# NTC_Thermistor_10K_VDiv.net
KiCad netlist of a schematic drawn in Altium Designer
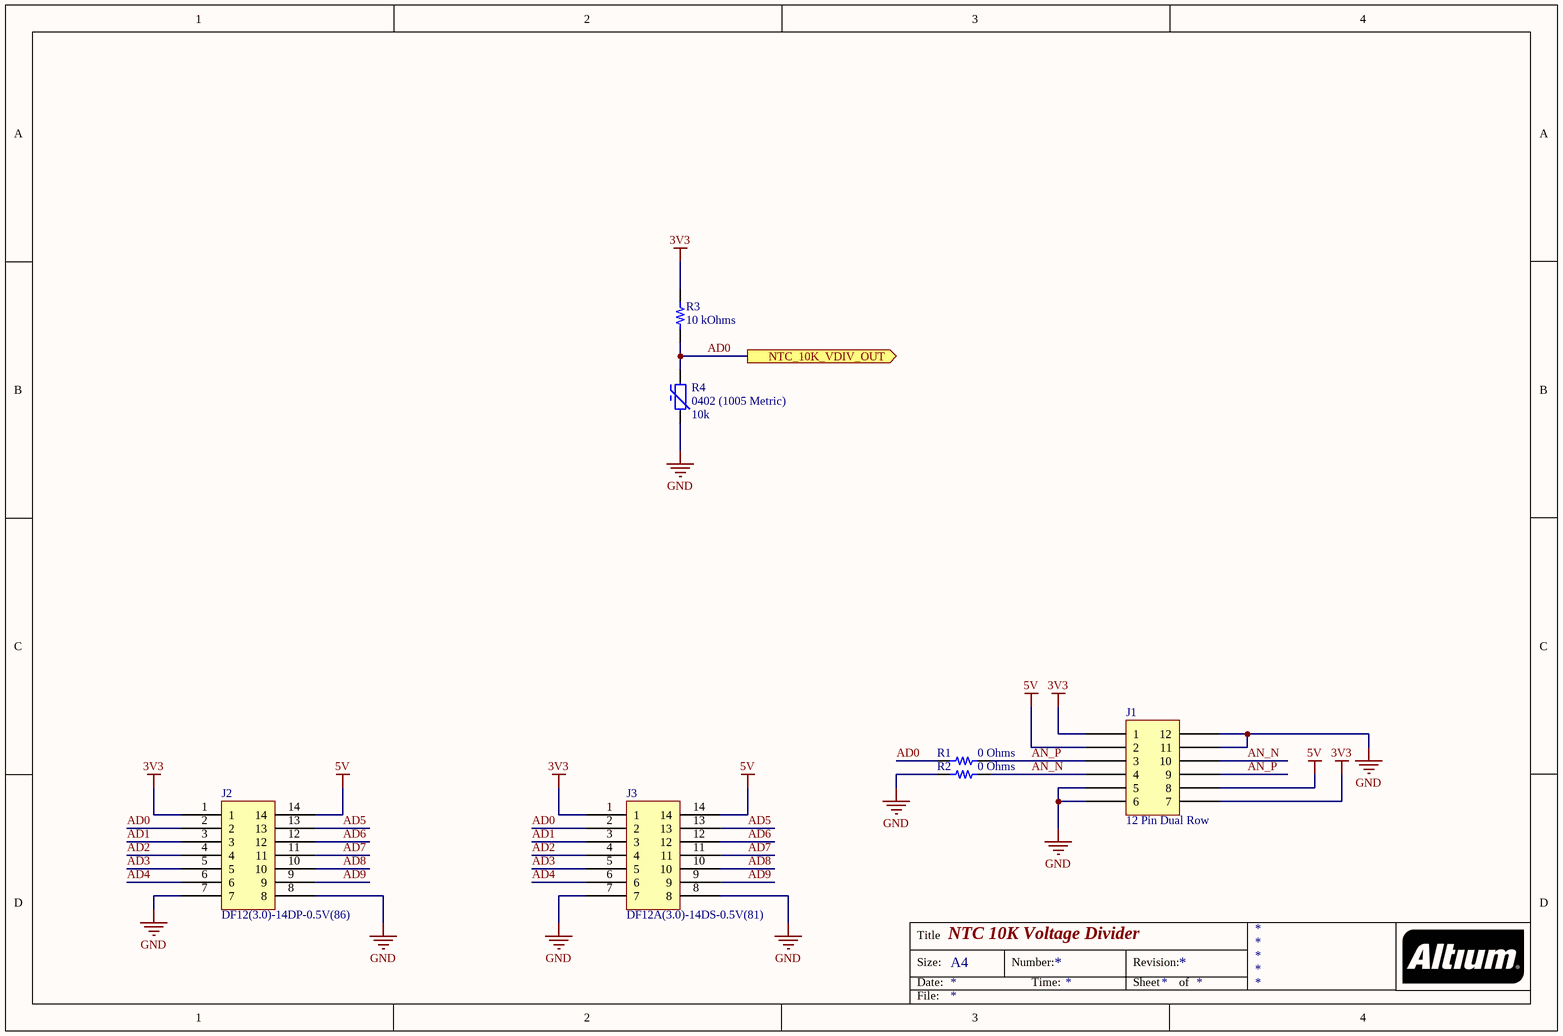
[diagram p0: NTC Thermistor 10K VDiv.SchDoc]

(export (version "E")
  (design (tool "Eeschema 10.0.6"))
  (components
    (comp (ref "J1")
      (value "12 Pin Dual Row")
      (footprint "TE 5650118-3 Card Edge")
      (libsource (lib "CelestialUseful") (part "12 Pin Dual Row"))
    )
    (comp (ref "J2")
      (value "DF12(3.0)-14DP-0.5V(86)")
      (footprint "HIROSE DF12 3.0-14DP-0.5V 86")
      (description "CONN HDR 14POS SMD GOLD")
      (fields (field (name "MANUFACTURER") "Hirose Electric Co Ltd"))
      (libsource (lib "altiumlibrary.com") (part "14 Pin Dual Row"))
    )
    (comp (ref "J3")
      (value "DF12A(3.0)-14DS-0.5V(81)")
      (footprint "HIROSE DF12A 3.0-14DS-0.5V 81")
      (description "CONN RCPT 14POS SMD GOLD")
      (fields (field (name "MANUFACTURER") "Hirose Electric Co Ltd"))
      (libsource (lib "altiumlibrary.com") (part "14 Pin Dual Row"))
    )
    (comp (ref "R1")
      (value "0 Ohms")
      (footprint "RES 0603_1608")
      (description "RES SMD 0 OHM JUMPER 1/10W 0603")
      (fields
        (field (name "PART NUMBER") "ERJ-3GEY0R00V")
        (field (name "MANUFACTURER") "Panasonic Electronic Components")
      )
      (libsource (lib "altiumlibrary.com") (part "Resistor"))
    )
    (comp (ref "R2")
      (value "0 Ohms")
      (footprint "RES 0603_1608")
      (description "RES SMD 0 OHM JUMPER 1/10W 0603")
      (fields
        (field (name "PART NUMBER") "ERJ-3GEY0R00V")
        (field (name "MANUFACTURER") "Panasonic Electronic Components")
      )
      (libsource (lib "altiumlibrary.com") (part "Resistor"))
    )
    (comp (ref "R3")
      (value "10 kOhms")
      (footprint "RES 0603_1608")
      (description "RES SMD 10K OHM 1% 1/10W 0603")
      (fields
        (field (name "PART NUMBER") "ERJ-3EKF1002V")
        (field (name "MANUFACTURER") "Panasonic Electronic Components")
      )
      (libsource (lib "altiumlibrary.com") (part "Resistor"))
    )
    (comp (ref "R4")
      (value "NCP15XH103F03RC")
      (footprint "NTC 0402_1005")
      (description "THERMISTOR NTC 10KOHM 3380K 0402")
      (fields
        (field (name "MANUFACTURER") "Murata Electronics")
        (field (name "PACKAGE / CASE") "0402 (1005 Metric)")
        (field (name "RESISTANCE IN OHMS @ 25°C") "10k")
      )
      (libsource (lib "altiumlibrary.com") (part "Thermistor"))
    )
  )
  (nets
    (net (code "1") (name "/AD0") (class "Default")
      (node (ref "J2") (pin "2") (pinfunction "2_2") (pintype "passive"))
      (node (ref "J3") (pin "2") (pinfunction "2_2") (pintype "passive"))
      (node (ref "R1") (pin "1") (pinfunction "1_1") (pintype "passive"))
      (node (ref "R3") (pin "1") (pinfunction "1_1") (pintype "passive"))
      (node (ref "R4") (pin "1") (pinfunction "1_1") (pintype "passive"))
    )
    (net (code "2") (name "/AD1") (class "Default")
      (node (ref "J2") (pin "3") (pinfunction "3_3") (pintype "passive"))
      (node (ref "J3") (pin "3") (pinfunction "3_3") (pintype "passive"))
    )
    (net (code "3") (name "/AD2") (class "Default")
      (node (ref "J2") (pin "4") (pinfunction "4_4") (pintype "passive"))
      (node (ref "J3") (pin "4") (pinfunction "4_4") (pintype "passive"))
    )
    (net (code "4") (name "/AD3") (class "Default")
      (node (ref "J2") (pin "5") (pinfunction "5_5") (pintype "passive"))
      (node (ref "J3") (pin "5") (pinfunction "5_5") (pintype "passive"))
    )
    (net (code "5") (name "/AD4") (class "Default")
      (node (ref "J2") (pin "6") (pinfunction "6_6") (pintype "passive"))
      (node (ref "J3") (pin "6") (pinfunction "6_6") (pintype "passive"))
    )
    (net (code "6") (name "/AD5") (class "Default")
      (node (ref "J2") (pin "13") (pinfunction "13_13") (pintype "passive"))
      (node (ref "J3") (pin "13") (pinfunction "13_13") (pintype "passive"))
    )
    (net (code "7") (name "/AD6") (class "Default")
      (node (ref "J2") (pin "12") (pinfunction "12_12") (pintype "passive"))
      (node (ref "J3") (pin "12") (pinfunction "12_12") (pintype "passive"))
    )
    (net (code "8") (name "/AD7") (class "Default")
      (node (ref "J2") (pin "11") (pinfunction "11_11") (pintype "passive"))
      (node (ref "J3") (pin "11") (pinfunction "11_11") (pintype "passive"))
    )
    (net (code "9") (name "/AD8") (class "Default")
      (node (ref "J2") (pin "10") (pinfunction "10_10") (pintype "passive"))
      (node (ref "J3") (pin "10") (pinfunction "10_10") (pintype "passive"))
    )
    (net (code "10") (name "/AD9") (class "Default")
      (node (ref "J2") (pin "9") (pinfunction "9_9") (pintype "passive"))
      (node (ref "J3") (pin "9") (pinfunction "9_9") (pintype "passive"))
    )
    (net (code "11") (name "/AN_N") (class "Default")
      (node (ref "J1") (pin "10") (pinfunction "10_10") (pintype "passive"))
      (node (ref "J1") (pin "4") (pinfunction "4_4") (pintype "passive"))
      (node (ref "R2") (pin "2") (pinfunction "2_2") (pintype "passive"))
    )
    (net (code "12") (name "/AN_P") (class "Default")
      (node (ref "J1") (pin "3") (pinfunction "3_3") (pintype "passive"))
      (node (ref "J1") (pin "9") (pinfunction "9_9") (pintype "passive"))
      (node (ref "R1") (pin "2") (pinfunction "2_2") (pintype "passive"))
    )
    (net (code "13") (name "3V3") (class "Default")
      (node (ref "J1") (pin "1") (pinfunction "1_1") (pintype "passive"))
      (node (ref "J1") (pin "7") (pinfunction "7_7") (pintype "passive"))
      (node (ref "J2") (pin "1") (pinfunction "1_1") (pintype "passive"))
      (node (ref "J3") (pin "1") (pinfunction "1_1") (pintype "passive"))
      (node (ref "R3") (pin "2") (pinfunction "2_2") (pintype "passive"))
    )
    (net (code "14") (name "5V") (class "Default")
      (node (ref "J1") (pin "2") (pinfunction "2_2") (pintype "passive"))
      (node (ref "J1") (pin "8") (pinfunction "8_8") (pintype "passive"))
      (node (ref "J2") (pin "14") (pinfunction "14_14") (pintype "passive"))
      (node (ref "J3") (pin "14") (pinfunction "14_14") (pintype "passive"))
    )
    (net (code "15") (name "GND") (class "Default")
      (node (ref "J1") (pin "11") (pinfunction "11_11") (pintype "passive"))
      (node (ref "J1") (pin "12") (pinfunction "12_12") (pintype "passive"))
      (node (ref "J1") (pin "5") (pinfunction "5_5") (pintype "passive"))
      (node (ref "J1") (pin "6") (pinfunction "6_6") (pintype "passive"))
      (node (ref "J2") (pin "7") (pinfunction "7_7") (pintype "passive"))
      (node (ref "J2") (pin "8") (pinfunction "8_8") (pintype "passive"))
      (node (ref "J3") (pin "7") (pinfunction "7_7") (pintype "passive"))
      (node (ref "J3") (pin "8") (pinfunction "8_8") (pintype "passive"))
      (node (ref "R2") (pin "1") (pinfunction "1_1") (pintype "passive"))
      (node (ref "R4") (pin "2") (pinfunction "2_2") (pintype "passive"))
    )
  )
)
